# Blade-Side_Schematic.net
KiCad netlist of a schematic drawn in Altium Designer
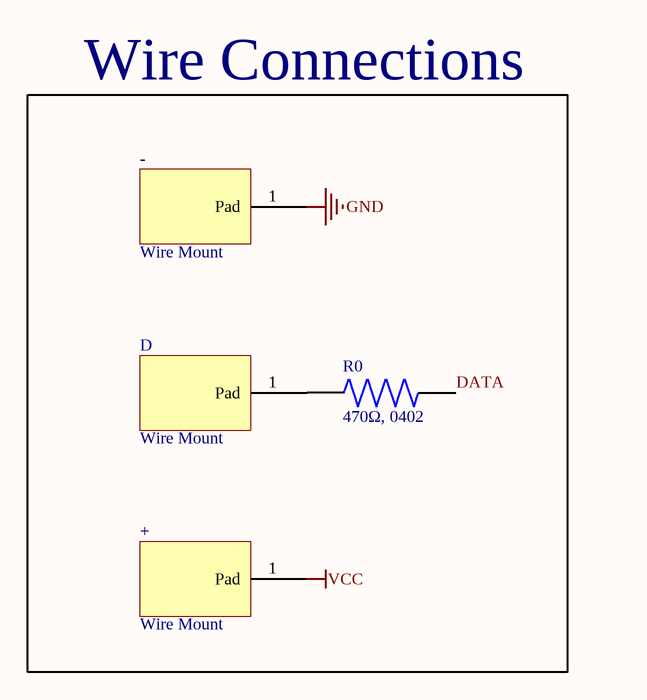
[diagram p0: Blade-Side Schematic.SchDoc]

(export (version "E")
  (design (tool "Eeschema 10.0.6"))
  (components
    (comp (ref "+")
      (value "Wire Mount")
      (footprint "Wire Mount")
      (libsource (lib "Lightsaber") (part "Wire Mount"))
    )
    (comp (ref "-")
      (value "Wire Mount")
      (footprint "Wire Mount")
      (libsource (lib "Lightsaber") (part "Wire Mount"))
    )
    (comp (ref "D")
      (value "Wire Mount")
      (footprint "Wire Mount")
      (libsource (lib "Lightsaber") (part "Wire Mount"))
    )
    (comp (ref "R0")
      (value "470Ω, 0402")
      (footprint "0402")
      (libsource (lib "Lightsaber") (part "Resistor, 0402"))
    )
  )
  (nets
    (net (code "1") (name "/DATA") (class "Default")
      (node (ref "R0") (pin "2") (pinfunction "2_2") (pintype "passive"))
    )
    (net (code "2") (name "GND") (class "Default")
      (node (ref "-") (pin "1") (pinfunction "Pad_1") (pintype "passive"))
    )
    (net (code "3") (name "Net-(D-Pad)") (class "Default")
      (node (ref "D") (pin "1") (pinfunction "Pad_1") (pintype "passive"))
      (node (ref "R0") (pin "1") (pinfunction "1_1") (pintype "passive"))
    )
    (net (code "4") (name "VCC") (class "Default")
      (node (ref "+") (pin "1") (pinfunction "Pad_1") (pintype "passive"))
    )
  )
)
